# PCB.net
KiCad netlist of a schematic drawn in EAGLE
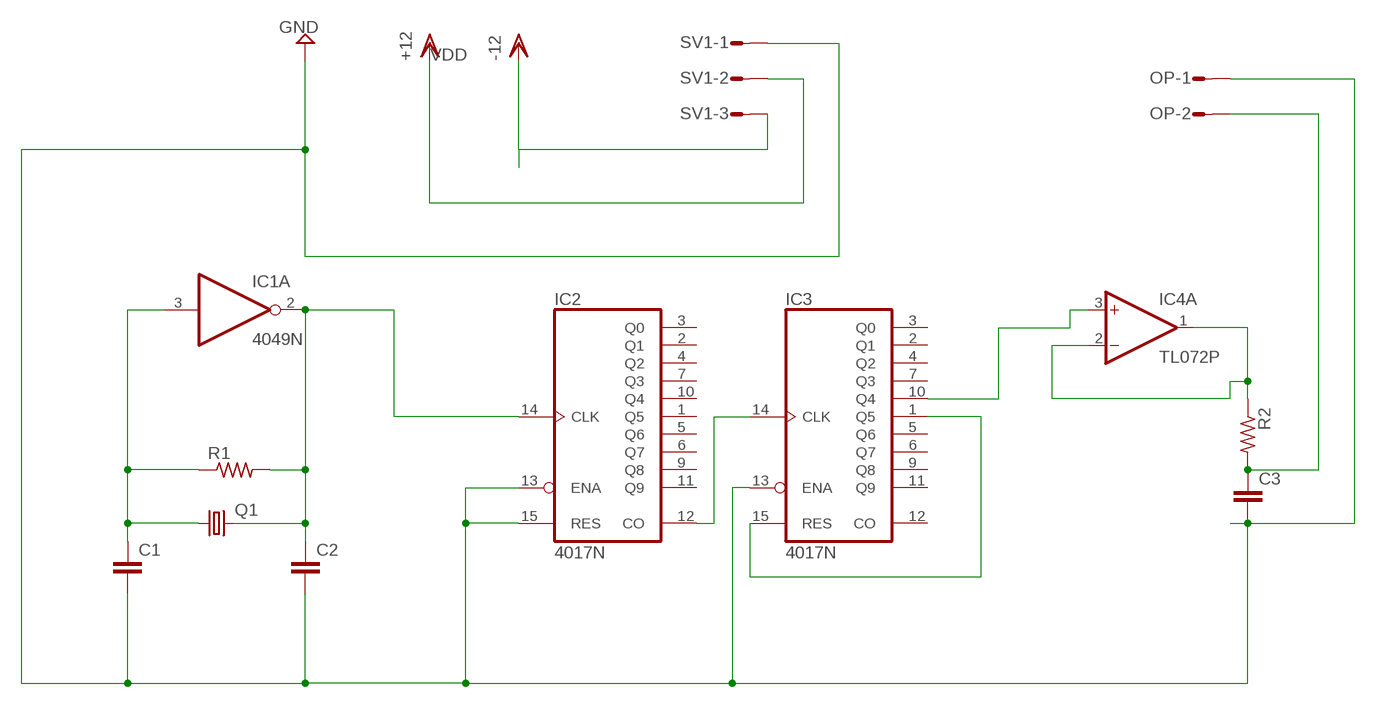
[diagram p0: schematic, sheet 1]

(export (version "E")
  (design (tool "Eeschema 10.0.6"))
  (components
    (comp (ref "C1")
      (value "C5/3.5")
      (footprint "eagle-import:C5B3.5")
      (libsource (lib "eagle-import") (part "C5/3.5"))
    )
    (comp (ref "C2")
      (value "C5/3.5")
      (footprint "eagle-import:C5B3.5")
      (libsource (lib "eagle-import") (part "C5/3.5"))
    )
    (comp (ref "C3")
      (value "C5/3.5")
      (footprint "eagle-import:C5B3.5")
      (libsource (lib "eagle-import") (part "C5/3.5"))
    )
    (comp (ref "IC1")
      (value "4049N")
      (footprint "eagle-import:DIL16")
      (libsource (lib "eagle-import") (part "4049N"))
    )
    (comp (ref "IC2")
      (value "4017N")
      (footprint "eagle-import:DIL16")
      (libsource (lib "eagle-import") (part "4017N"))
    )
    (comp (ref "IC3")
      (value "4017N")
      (footprint "eagle-import:DIL16")
      (libsource (lib "eagle-import") (part "4017N"))
    )
    (comp (ref "IC4")
      (value "TL072P")
      (footprint "eagle-import:DIL08")
      (libsource (lib "eagle-import") (part "TL072P"))
    )
    (comp (ref "OP")
      (value "L02P")
      (footprint "eagle-import:L02P")
      (libsource (lib "eagle-import") (part "L02P"))
    )
    (comp (ref "Q1")
      (value "CRYSTALHC33U-V")
      (footprint "eagle-import:HC33U-V")
      (libsource (lib "eagle-import") (part "CRYSTALHC33U-V"))
    )
    (comp (ref "R1")
      (value "R-US_0207/12")
      (footprint "eagle-import:0207_12")
      (libsource (lib "eagle-import") (part "R-US_0207/12"))
    )
    (comp (ref "R2")
      (value "R-US_0207/12")
      (footprint "eagle-import:0207_12")
      (libsource (lib "eagle-import") (part "R-US_0207/12"))
    )
    (comp (ref "SV1")
      (value "L03P")
      (footprint "eagle-import:L03P")
      (libsource (lib "eagle-import") (part "L03P"))
    )
  )
  (nets
    (net (code "1") (name "+12") (class "Default")
      (node (ref "SV1") (pin "2") (pinfunction "S_2") (pintype "passive"))
      (node (ref "SV1") (pin "3") (pinfunction "S_3") (pintype "passive"))
    )
    (net (code "2") (name "GND") (class "Default")
      (node (ref "C1") (pin "2") (pinfunction "2_2") (pintype "passive"))
      (node (ref "C2") (pin "2") (pinfunction "2_2") (pintype "passive"))
      (node (ref "C3") (pin "2") (pinfunction "2_2") (pintype "passive"))
      (node (ref "IC2") (pin "13") (pinfunction "ENA_13") (pintype "input"))
      (node (ref "IC2") (pin "15") (pinfunction "RES_15") (pintype "input"))
      (node (ref "IC3") (pin "13") (pinfunction "ENA_13") (pintype "input"))
      (node (ref "OP") (pin "1") (pinfunction "S_1") (pintype "passive"))
      (node (ref "SV1") (pin "1") (pinfunction "S_1") (pintype "passive"))
    )
    (net (code "3") (name "Net-(IC1A-I)") (class "Default")
      (node (ref "C1") (pin "1") (pinfunction "1_1") (pintype "passive"))
      (node (ref "IC1") (pin "3") (pinfunction "I_3") (pintype "input"))
      (node (ref "Q1") (pin "1") (pinfunction "1_1") (pintype "passive"))
      (node (ref "R1") (pin "1") (pinfunction "1_1") (pintype "passive"))
    )
    (net (code "4") (name "Net-(IC1A-O)") (class "Default")
      (node (ref "C2") (pin "1") (pinfunction "1_1") (pintype "passive"))
      (node (ref "IC1") (pin "2") (pinfunction "O_2") (pintype "output"))
      (node (ref "IC2") (pin "14") (pinfunction "CLK_14") (pintype "input"))
      (node (ref "Q1") (pin "2") (pinfunction "2_2") (pintype "passive"))
      (node (ref "R1") (pin "2") (pinfunction "2_2") (pintype "passive"))
    )
    (net (code "5") (name "Net-(IC2A-CO)") (class "Default")
      (node (ref "IC2") (pin "12") (pinfunction "CO_12") (pintype "output"))
      (node (ref "IC3") (pin "14") (pinfunction "CLK_14") (pintype "input"))
    )
    (net (code "6") (name "Net-(IC3A-Q4)") (class "Default")
      (node (ref "IC3") (pin "10") (pinfunction "Q4_10") (pintype "output"))
      (node (ref "IC4") (pin "3") (pinfunction "+IN_3") (pintype "input"))
    )
    (net (code "7") (name "Net-(IC3A-Q5)") (class "Default")
      (node (ref "IC3") (pin "1") (pinfunction "Q5_1") (pintype "output"))
      (node (ref "IC3") (pin "15") (pinfunction "RES_15") (pintype "input"))
    )
    (net (code "8") (name "Net-(IC4A--IN)") (class "Default")
      (node (ref "IC4") (pin "1") (pinfunction "OUT_1") (pintype "output"))
      (node (ref "IC4") (pin "2") (pinfunction "-IN_2") (pintype "input"))
      (node (ref "R2") (pin "1") (pinfunction "1_1") (pintype "passive"))
    )
    (net (code "9") (name "Net-(OPB-S)") (class "Default")
      (node (ref "C3") (pin "1") (pinfunction "1_1") (pintype "passive"))
      (node (ref "OP") (pin "2") (pinfunction "S_2") (pintype "passive"))
      (node (ref "R2") (pin "2") (pinfunction "2_2") (pintype "passive"))
    )
    (net (code "10") (name "unconnected-(IC2A-Q0-Pad3)") (class "Default")
      (node (ref "IC2") (pin "3") (pinfunction "Q0_3") (pintype "output"))
    )
    (net (code "11") (name "unconnected-(IC2A-Q1-Pad2)") (class "Default")
      (node (ref "IC2") (pin "2") (pinfunction "Q1_2") (pintype "output"))
    )
    (net (code "12") (name "unconnected-(IC2A-Q2-Pad4)") (class "Default")
      (node (ref "IC2") (pin "4") (pinfunction "Q2_4") (pintype "output"))
    )
    (net (code "13") (name "unconnected-(IC2A-Q3-Pad7)") (class "Default")
      (node (ref "IC2") (pin "7") (pinfunction "Q3_7") (pintype "output"))
    )
    (net (code "14") (name "unconnected-(IC2A-Q4-Pad10)") (class "Default")
      (node (ref "IC2") (pin "10") (pinfunction "Q4_10") (pintype "output"))
    )
    (net (code "15") (name "unconnected-(IC2A-Q5-Pad1)") (class "Default")
      (node (ref "IC2") (pin "1") (pinfunction "Q5_1") (pintype "output"))
    )
    (net (code "16") (name "unconnected-(IC2A-Q6-Pad5)") (class "Default")
      (node (ref "IC2") (pin "5") (pinfunction "Q6_5") (pintype "output"))
    )
    (net (code "17") (name "unconnected-(IC2A-Q7-Pad6)") (class "Default")
      (node (ref "IC2") (pin "6") (pinfunction "Q7_6") (pintype "output"))
    )
    (net (code "18") (name "unconnected-(IC2A-Q8-Pad9)") (class "Default")
      (node (ref "IC2") (pin "9") (pinfunction "Q8_9") (pintype "output"))
    )
    (net (code "19") (name "unconnected-(IC2A-Q9-Pad11)") (class "Default")
      (node (ref "IC2") (pin "11") (pinfunction "Q9_11") (pintype "output"))
    )
    (net (code "20") (name "unconnected-(IC3A-CO-Pad12)") (class "Default")
      (node (ref "IC3") (pin "12") (pinfunction "CO_12") (pintype "output"))
    )
    (net (code "21") (name "unconnected-(IC3A-Q0-Pad3)") (class "Default")
      (node (ref "IC3") (pin "3") (pinfunction "Q0_3") (pintype "output"))
    )
    (net (code "22") (name "unconnected-(IC3A-Q1-Pad2)") (class "Default")
      (node (ref "IC3") (pin "2") (pinfunction "Q1_2") (pintype "output"))
    )
    (net (code "23") (name "unconnected-(IC3A-Q2-Pad4)") (class "Default")
      (node (ref "IC3") (pin "4") (pinfunction "Q2_4") (pintype "output"))
    )
    (net (code "24") (name "unconnected-(IC3A-Q3-Pad7)") (class "Default")
      (node (ref "IC3") (pin "7") (pinfunction "Q3_7") (pintype "output"))
    )
    (net (code "25") (name "unconnected-(IC3A-Q6-Pad5)") (class "Default")
      (node (ref "IC3") (pin "5") (pinfunction "Q6_5") (pintype "output"))
    )
    (net (code "26") (name "unconnected-(IC3A-Q7-Pad6)") (class "Default")
      (node (ref "IC3") (pin "6") (pinfunction "Q7_6") (pintype "output"))
    )
    (net (code "27") (name "unconnected-(IC3A-Q8-Pad9)") (class "Default")
      (node (ref "IC3") (pin "9") (pinfunction "Q8_9") (pintype "output"))
    )
    (net (code "28") (name "unconnected-(IC3A-Q9-Pad11)") (class "Default")
      (node (ref "IC3") (pin "11") (pinfunction "Q9_11") (pintype "output"))
    )
  )
)
